# TP1_Embebidos.net
KiCad netlist of a schematic drawn in Altium Designer
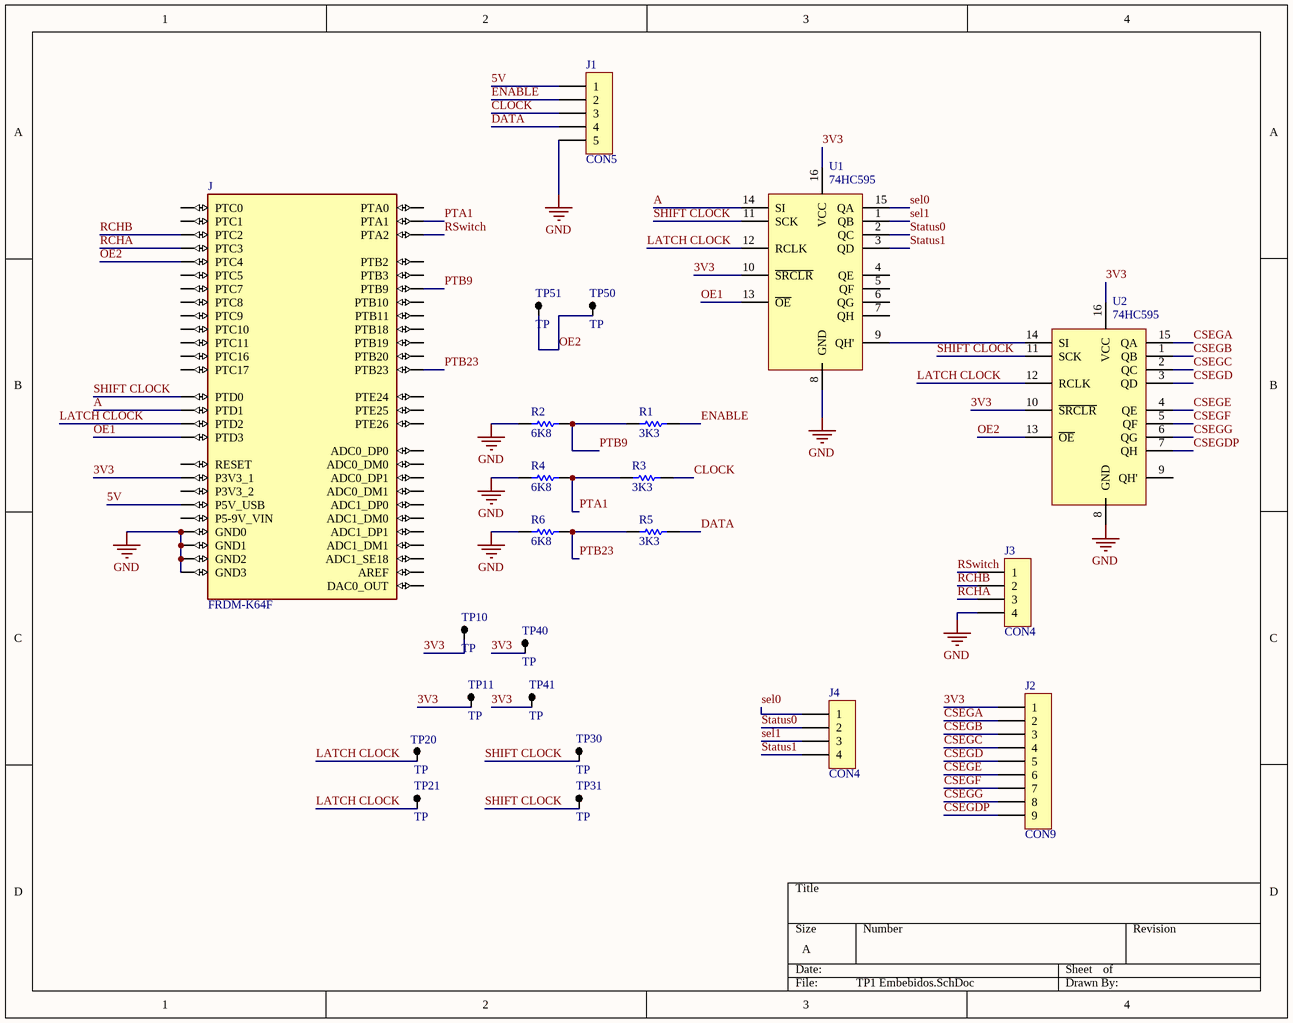
[diagram p0: TP1 Embebidos.SchDoc]

(export (version "E")
  (design (tool "Eeschema 10.0.6"))
  (components
    (comp (ref "J")
      (value "FRDM-K64F")
      (footprint "FRDM-K64F")
      (fields (field (name "MF") "NXP USA"))
      (libsource (lib "FRDM-K64F") (part "FRDM-K64F"))
    )
    (comp (ref "J1") (value "CON5") (footprint "SIP5") (libsource (lib "LIBEBAL") (part "CON5")))
    (comp (ref "J2") (value "CON9") (footprint "SIP9") (libsource (lib "LIBEBAL") (part "CON9")))
    (comp (ref "J3") (value "CON4") (footprint "SIP4") (libsource (lib "LIBEBAL") (part "CON4")))
    (comp (ref "J4") (value "CON4") (footprint "SIP4") (libsource (lib "LIBEBAL") (part "CON4")))
    (comp (ref "R1") (value "3K3") (footprint "RES400") (libsource (lib "LIBEBAL") (part "RES")))
    (comp (ref "R2") (value "6K8") (footprint "RES400") (libsource (lib "LIBEBAL") (part "RES")))
    (comp (ref "R3") (value "3K3") (footprint "RES400") (libsource (lib "LIBEBAL") (part "RES")))
    (comp (ref "R4") (value "6K8") (footprint "RES400") (libsource (lib "LIBEBAL") (part "RES")))
    (comp (ref "R5") (value "3K3") (footprint "RES400") (libsource (lib "LIBEBAL") (part "RES")))
    (comp (ref "R6") (value "6K8") (footprint "RES400") (libsource (lib "LIBEBAL") (part "RES")))
    (comp (ref "TP10") (value "TP") (footprint "TPTH") (libsource (lib "LIBEBAL") (part "TP")))
    (comp (ref "TP11") (value "TP") (footprint "TPTH") (libsource (lib "LIBEBAL") (part "TP")))
    (comp (ref "TP20") (value "TP") (footprint "TPTH") (libsource (lib "LIBEBAL") (part "TP")))
    (comp (ref "TP21") (value "TP") (footprint "TPTH") (libsource (lib "LIBEBAL") (part "TP")))
    (comp (ref "TP30") (value "TP") (footprint "TPTH") (libsource (lib "LIBEBAL") (part "TP")))
    (comp (ref "TP31") (value "TP") (footprint "TPTH") (libsource (lib "LIBEBAL") (part "TP")))
    (comp (ref "TP40") (value "TP") (footprint "TPTH") (libsource (lib "LIBEBAL") (part "TP")))
    (comp (ref "TP41") (value "TP") (footprint "TPTH") (libsource (lib "LIBEBAL") (part "TP")))
    (comp (ref "TP50") (value "TP") (footprint "TPTH") (libsource (lib "LIBEBAL") (part "TP")))
    (comp (ref "TP51") (value "TP") (footprint "TPTH") (libsource (lib "LIBEBAL") (part "TP")))
    (comp (ref "U1") (value "74HC595") (footprint "DIP16") (libsource (lib "LIBEBAL") (part "74HC595")))
    (comp (ref "U2") (value "74HC595") (footprint "DIP16") (libsource (lib "LIBEBAL") (part "74HC595")))
  )
  (nets
    (net (code "1") (name "/3V3") (class "Default")
      (node (ref "J") (pin "J3-4") (pinfunction "P3V3_1_J3-4") (pintype "bidirectional"))
      (node (ref "J2") (pin "1") (pinfunction "1_1") (pintype "passive"))
      (node (ref "TP10") (pin "1") (pinfunction "1_1") (pintype "passive"))
      (node (ref "TP11") (pin "1") (pinfunction "1_1") (pintype "passive"))
      (node (ref "TP40") (pin "1") (pinfunction "1_1") (pintype "passive"))
      (node (ref "TP41") (pin "1") (pinfunction "1_1") (pintype "passive"))
      (node (ref "U1") (pin "10") (pinfunction "~{SRCLR}_10") (pintype "passive"))
      (node (ref "U1") (pin "16") (pinfunction "VCC_16") (pintype "passive"))
      (node (ref "U2") (pin "10") (pinfunction "~{SRCLR}_10") (pintype "passive"))
      (node (ref "U2") (pin "16") (pinfunction "VCC_16") (pintype "passive"))
    )
    (net (code "2") (name "/5V") (class "Default")
      (node (ref "J") (pin "J3-10") (pinfunction "P5V_USB_J3-10") (pintype "bidirectional"))
      (node (ref "J1") (pin "1") (pinfunction "1_1") (pintype "passive"))
    )
    (net (code "3") (name "/A") (class "Default")
      (node (ref "J") (pin "J2-12") (pinfunction "PTD1_J2-12") (pintype "bidirectional"))
      (node (ref "U1") (pin "14") (pinfunction "SI_14") (pintype "passive"))
    )
    (net (code "4") (name "/CLOCK") (class "Default")
      (node (ref "J1") (pin "3") (pinfunction "3_3") (pintype "passive"))
      (node (ref "R3") (pin "2") (pinfunction "2_2") (pintype "passive"))
    )
    (net (code "5") (name "/CSEGA") (class "Default")
      (node (ref "J2") (pin "2") (pinfunction "2_2") (pintype "passive"))
      (node (ref "U2") (pin "15") (pinfunction "QA_15") (pintype "passive"))
    )
    (net (code "6") (name "/CSEGB") (class "Default")
      (node (ref "J2") (pin "3") (pinfunction "3_3") (pintype "passive"))
      (node (ref "U2") (pin "1") (pinfunction "QB_1") (pintype "passive"))
    )
    (net (code "7") (name "/CSEGC") (class "Default")
      (node (ref "J2") (pin "4") (pinfunction "4_4") (pintype "passive"))
      (node (ref "U2") (pin "2") (pinfunction "QC_2") (pintype "passive"))
    )
    (net (code "8") (name "/CSEGD") (class "Default")
      (node (ref "J2") (pin "5") (pinfunction "5_5") (pintype "passive"))
      (node (ref "U2") (pin "3") (pinfunction "QD_3") (pintype "passive"))
    )
    (net (code "9") (name "/CSEGDP") (class "Default")
      (node (ref "J2") (pin "9") (pinfunction "9_9") (pintype "passive"))
      (node (ref "U2") (pin "7") (pinfunction "QH_7") (pintype "passive"))
    )
    (net (code "10") (name "/CSEGE") (class "Default")
      (node (ref "J2") (pin "6") (pinfunction "6_6") (pintype "passive"))
      (node (ref "U2") (pin "4") (pinfunction "QE_4") (pintype "passive"))
    )
    (net (code "11") (name "/CSEGF") (class "Default")
      (node (ref "J2") (pin "7") (pinfunction "7_7") (pintype "passive"))
      (node (ref "U2") (pin "5") (pinfunction "QF_5") (pintype "passive"))
    )
    (net (code "12") (name "/CSEGG") (class "Default")
      (node (ref "J2") (pin "8") (pinfunction "8_8") (pintype "passive"))
      (node (ref "U2") (pin "6") (pinfunction "QG_6") (pintype "passive"))
    )
    (net (code "13") (name "/DATA") (class "Default")
      (node (ref "J1") (pin "4") (pinfunction "4_4") (pintype "passive"))
      (node (ref "R5") (pin "2") (pinfunction "2_2") (pintype "passive"))
    )
    (net (code "14") (name "/ENABLE") (class "Default")
      (node (ref "J1") (pin "2") (pinfunction "2_2") (pintype "passive"))
      (node (ref "R1") (pin "2") (pinfunction "2_2") (pintype "passive"))
    )
    (net (code "15") (name "/LATCH CLOCK") (class "Default")
      (node (ref "J") (pin "J2-8") (pinfunction "PTD2_J2-8") (pintype "bidirectional"))
      (node (ref "TP20") (pin "1") (pinfunction "1_1") (pintype "passive"))
      (node (ref "TP21") (pin "1") (pinfunction "1_1") (pintype "passive"))
      (node (ref "U1") (pin "12") (pinfunction "RCLK_12") (pintype "passive"))
      (node (ref "U2") (pin "12") (pinfunction "RCLK_12") (pintype "passive"))
    )
    (net (code "16") (name "/OE1") (class "Default")
      (node (ref "J") (pin "J2-10") (pinfunction "PTD3_J2-10") (pintype "bidirectional"))
      (node (ref "U1") (pin "13") (pinfunction "~{OE}_13") (pintype "passive"))
    )
    (net (code "17") (name "/OE2") (class "Default")
      (node (ref "J") (pin "J2-4") (pinfunction "PTC4_J2-4") (pintype "bidirectional"))
      (node (ref "TP50") (pin "1") (pinfunction "1_1") (pintype "passive"))
      (node (ref "TP51") (pin "1") (pinfunction "1_1") (pintype "passive"))
      (node (ref "U2") (pin "13") (pinfunction "~{OE}_13") (pintype "passive"))
    )
    (net (code "18") (name "/PTA1") (class "Default")
      (node (ref "J") (pin "J1-8") (pinfunction "PTA1_J1-8") (pintype "bidirectional"))
      (node (ref "R3") (pin "1") (pinfunction "1_1") (pintype "passive"))
      (node (ref "R4") (pin "2") (pinfunction "2_2") (pintype "passive"))
    )
    (net (code "19") (name "/PTB9") (class "Default")
      (node (ref "J") (pin "J1-6") (pinfunction "PTB9_J1-6") (pintype "bidirectional"))
      (node (ref "R1") (pin "1") (pinfunction "1_1") (pintype "passive"))
      (node (ref "R2") (pin "2") (pinfunction "2_2") (pintype "passive"))
    )
    (net (code "20") (name "/PTB23") (class "Default")
      (node (ref "J") (pin "J1-10") (pinfunction "PTB23_J1-10") (pintype "bidirectional"))
      (node (ref "R5") (pin "1") (pinfunction "1_1") (pintype "passive"))
      (node (ref "R6") (pin "2") (pinfunction "2_2") (pintype "passive"))
    )
    (net (code "21") (name "/RCHA") (class "Default")
      (node (ref "J") (pin "J1-16") (pinfunction "PTC3_J1-16") (pintype "bidirectional"))
      (node (ref "J3") (pin "3") (pinfunction "3_3") (pintype "passive"))
    )
    (net (code "22") (name "/RCHB") (class "Default")
      (node (ref "J") (pin "J1-14") (pinfunction "PTC2_J1-14") (pintype "bidirectional"))
      (node (ref "J3") (pin "2") (pinfunction "2_2") (pintype "passive"))
    )
    (net (code "23") (name "/RSwitch") (class "Default")
      (node (ref "J") (pin "J1-12") (pinfunction "PTA2_J1-12") (pintype "bidirectional"))
      (node (ref "J3") (pin "1") (pinfunction "1_1") (pintype "passive"))
    )
    (net (code "24") (name "/SHIFT CLOCK") (class "Default")
      (node (ref "J") (pin "J2-6") (pinfunction "PTD0_J2-6") (pintype "bidirectional"))
      (node (ref "TP30") (pin "1") (pinfunction "1_1") (pintype "passive"))
      (node (ref "TP31") (pin "1") (pinfunction "1_1") (pintype "passive"))
      (node (ref "U1") (pin "11") (pinfunction "SCK_11") (pintype "passive"))
      (node (ref "U2") (pin "11") (pinfunction "SCK_11") (pintype "passive"))
    )
    (net (code "25") (name "/Status0") (class "Default")
      (node (ref "J4") (pin "2") (pinfunction "2_2") (pintype "passive"))
      (node (ref "U1") (pin "2") (pinfunction "QC_2") (pintype "passive"))
    )
    (net (code "26") (name "/Status1") (class "Default")
      (node (ref "J4") (pin "4") (pinfunction "4_4") (pintype "passive"))
      (node (ref "U1") (pin "3") (pinfunction "QD_3") (pintype "passive"))
    )
    (net (code "27") (name "/sel0") (class "Default")
      (node (ref "J4") (pin "1") (pinfunction "1_1") (pintype "passive"))
      (node (ref "U1") (pin "15") (pinfunction "QA_15") (pintype "passive"))
    )
    (net (code "28") (name "/sel1") (class "Default")
      (node (ref "J4") (pin "3") (pinfunction "3_3") (pintype "passive"))
      (node (ref "U1") (pin "1") (pinfunction "QB_1") (pintype "passive"))
    )
    (net (code "29") (name "GND") (class "Default")
      (node (ref "J") (pin "J2-14") (pinfunction "GND1_J2-14") (pintype "bidirectional"))
      (node (ref "J") (pin "J2-3") (pinfunction "GND0_J2-3") (pintype "bidirectional"))
      (node (ref "J") (pin "J3-12") (pinfunction "GND2_J3-12") (pintype "bidirectional"))
      (node (ref "J") (pin "J3-14") (pinfunction "GND3_J3-14") (pintype "bidirectional"))
      (node (ref "J1") (pin "5") (pinfunction "5_5") (pintype "passive"))
      (node (ref "J3") (pin "4") (pinfunction "4_4") (pintype "passive"))
      (node (ref "R2") (pin "1") (pinfunction "1_1") (pintype "passive"))
      (node (ref "R4") (pin "1") (pinfunction "1_1") (pintype "passive"))
      (node (ref "R6") (pin "1") (pinfunction "1_1") (pintype "passive"))
      (node (ref "U1") (pin "8") (pinfunction "GND_8") (pintype "passive"))
      (node (ref "U2") (pin "8") (pinfunction "GND_8") (pintype "passive"))
    )
    (net (code "30") (name "Net-(U1-QH')") (class "Default")
      (node (ref "U1") (pin "9") (pinfunction "QH'_9") (pintype "passive"))
      (node (ref "U2") (pin "14") (pinfunction "SI_14") (pintype "passive"))
    )
    (net (code "31") (name "unconnected-(J-ADC0_DM0-PadJ2-7)") (class "Default")
      (node (ref "J") (pin "J2-7") (pinfunction "ADC0_DM0_J2-7") (pintype "bidirectional"))
    )
    (net (code "32") (name "unconnected-(J-ADC0_DM1-PadJ4-3)") (class "Default")
      (node (ref "J") (pin "J4-3") (pinfunction "ADC0_DM1_J4-3") (pintype "bidirectional"))
    )
    (net (code "33") (name "unconnected-(J-ADC0_DP0-PadJ2-5)") (class "Default")
      (node (ref "J") (pin "J2-5") (pinfunction "ADC0_DP0_J2-5") (pintype "bidirectional"))
    )
    (net (code "34") (name "unconnected-(J-ADC0_DP1-PadJ4-1)") (class "Default")
      (node (ref "J") (pin "J4-1") (pinfunction "ADC0_DP1_J4-1") (pintype "bidirectional"))
    )
    (net (code "35") (name "unconnected-(J-ADC1_DM0-PadJ2-13)") (class "Default")
      (node (ref "J") (pin "J2-13") (pinfunction "ADC1_DM0_J2-13") (pintype "bidirectional"))
    )
    (net (code "36") (name "unconnected-(J-ADC1_DM1-PadJ4-7)") (class "Default")
      (node (ref "J") (pin "J4-7") (pinfunction "ADC1_DM1_J4-7") (pintype "bidirectional"))
    )
    (net (code "37") (name "unconnected-(J-ADC1_DP0-PadJ2-11)") (class "Default")
      (node (ref "J") (pin "J2-11") (pinfunction "ADC1_DP0_J2-11") (pintype "bidirectional"))
    )
    (net (code "38") (name "unconnected-(J-ADC1_DP1-PadJ4-5)") (class "Default")
      (node (ref "J") (pin "J4-5") (pinfunction "ADC1_DP1_J4-5") (pintype "bidirectional"))
    )
    (net (code "39") (name "unconnected-(J-ADC1_SE18-PadJ2-17)") (class "Default")
      (node (ref "J") (pin "J2-17") (pinfunction "ADC1_SE18_J2-17") (pintype "bidirectional"))
    )
    (net (code "40") (name "unconnected-(J-AREF-PadJ2-16)") (class "Default")
      (node (ref "J") (pin "J2-16") (pinfunction "AREF_J2-16") (pintype "bidirectional"))
    )
    (net (code "41") (name "unconnected-(J-DAC0_OUT-PadJ4-11)") (class "Default")
      (node (ref "J") (pin "J4-11") (pinfunction "DAC0_OUT_J4-11") (pintype "bidirectional"))
    )
    (net (code "42") (name "unconnected-(J-P3V3_2-PadJ3-8)") (class "Default")
      (node (ref "J") (pin "J3-8") (pinfunction "P3V3_2_J3-8") (pintype "bidirectional"))
    )
    (net (code "43") (name "unconnected-(J-P5-9V_VIN-PadJ3-16)") (class "Default")
      (node (ref "J") (pin "J3-16") (pinfunction "P5-9V_VIN_J3-16") (pintype "bidirectional"))
    )
    (net (code "44") (name "unconnected-(J-PTA0-PadJ2-2)") (class "Default")
      (node (ref "J") (pin "J2-2") (pinfunction "PTA0_J2-2") (pintype "bidirectional"))
    )
    (net (code "45") (name "unconnected-(J-PTB2-PadJ4-2)") (class "Default")
      (node (ref "J") (pin "J4-2") (pinfunction "PTB2_J4-2") (pintype "bidirectional"))
    )
    (net (code "46") (name "unconnected-(J-PTB3-PadJ4-4)") (class "Default")
      (node (ref "J") (pin "J4-4") (pinfunction "PTB3_J4-4") (pintype "bidirectional"))
    )
    (net (code "47") (name "unconnected-(J-PTB10-PadJ4-6)") (class "Default")
      (node (ref "J") (pin "J4-6") (pinfunction "PTB10_J4-6") (pintype "bidirectional"))
    )
    (net (code "48") (name "unconnected-(J-PTB11-PadJ4-8)") (class "Default")
      (node (ref "J") (pin "J4-8") (pinfunction "PTB11_J4-8") (pintype "bidirectional"))
    )
    (net (code "49") (name "unconnected-(J-PTB18-PadJ1-1)") (class "Default")
      (node (ref "J") (pin "J1-1") (pinfunction "PTB18_J1-1") (pintype "bidirectional"))
    )
    (net (code "50") (name "unconnected-(J-PTB19-PadJ1-3)") (class "Default")
      (node (ref "J") (pin "J1-3") (pinfunction "PTB19_J1-3") (pintype "bidirectional"))
    )
    (net (code "51") (name "unconnected-(J-PTB20-PadJ4-9)") (class "Default")
      (node (ref "J") (pin "J4-9") (pinfunction "PTB20_J4-9") (pintype "bidirectional"))
    )
    (net (code "52") (name "unconnected-(J-PTC0-PadJ1-11)") (class "Default")
      (node (ref "J") (pin "J1-11") (pinfunction "PTC0_J1-11") (pintype "bidirectional"))
    )
    (net (code "53") (name "unconnected-(J-PTC1-PadJ1-5)") (class "Default")
      (node (ref "J") (pin "J1-5") (pinfunction "PTC1_J1-5") (pintype "bidirectional"))
    )
    (net (code "54") (name "unconnected-(J-PTC5-PadJ1-15)") (class "Default")
      (node (ref "J") (pin "J1-15") (pinfunction "PTC5_J1-15") (pintype "bidirectional"))
    )
    (net (code "55") (name "unconnected-(J-PTC7-PadJ1-13)") (class "Default")
      (node (ref "J") (pin "J1-13") (pinfunction "PTC7_J1-13") (pintype "bidirectional"))
    )
    (net (code "56") (name "unconnected-(J-PTC8-PadJ1-7)") (class "Default")
      (node (ref "J") (pin "J1-7") (pinfunction "PTC8_J1-7") (pintype "bidirectional"))
    )
    (net (code "57") (name "unconnected-(J-PTC9-PadJ1-9)") (class "Default")
      (node (ref "J") (pin "J1-9") (pinfunction "PTC9_J1-9") (pintype "bidirectional"))
    )
    (net (code "58") (name "unconnected-(J-PTC10-PadJ4-12)") (class "Default")
      (node (ref "J") (pin "J4-12") (pinfunction "PTC10_J4-12") (pintype "bidirectional"))
    )
    (net (code "59") (name "unconnected-(J-PTC11-PadJ4-10)") (class "Default")
      (node (ref "J") (pin "J4-10") (pinfunction "PTC11_J4-10") (pintype "bidirectional"))
    )
    (net (code "60") (name "unconnected-(J-PTC16-PadJ1-2)") (class "Default")
      (node (ref "J") (pin "J1-2") (pinfunction "PTC16_J1-2") (pintype "bidirectional"))
    )
    (net (code "61") (name "unconnected-(J-PTC17-PadJ1-4)") (class "Default")
      (node (ref "J") (pin "J1-4") (pinfunction "PTC17_J1-4") (pintype "bidirectional"))
    )
    (net (code "62") (name "unconnected-(J-PTE24-PadJ2-20)") (class "Default")
      (node (ref "J") (pin "J2-20") (pinfunction "PTE24_J2-20") (pintype "bidirectional"))
    )
    (net (code "63") (name "unconnected-(J-PTE25-PadJ2-18)") (class "Default")
      (node (ref "J") (pin "J2-18") (pinfunction "PTE25_J2-18") (pintype "bidirectional"))
    )
    (net (code "64") (name "unconnected-(J-PTE26-PadJ2-1)") (class "Default")
      (node (ref "J") (pin "J2-1") (pinfunction "PTE26_J2-1") (pintype "bidirectional"))
    )
    (net (code "65") (name "unconnected-(J-RESET-PadJ3-6)") (class "Default")
      (node (ref "J") (pin "J3-6") (pinfunction "RESET_J3-6") (pintype "bidirectional"))
    )
    (net (code "66") (name "unconnected-(U1-QE-Pad4)") (class "Default")
      (node (ref "U1") (pin "4") (pinfunction "QE_4") (pintype "passive"))
    )
    (net (code "67") (name "unconnected-(U1-QF-Pad5)") (class "Default")
      (node (ref "U1") (pin "5") (pinfunction "QF_5") (pintype "passive"))
    )
    (net (code "68") (name "unconnected-(U1-QG-Pad6)") (class "Default")
      (node (ref "U1") (pin "6") (pinfunction "QG_6") (pintype "passive"))
    )
    (net (code "69") (name "unconnected-(U1-QH-Pad7)") (class "Default")
      (node (ref "U1") (pin "7") (pinfunction "QH_7") (pintype "passive"))
    )
    (net (code "70") (name "unconnected-(U2-QH'-Pad9)") (class "Default")
      (node (ref "U2") (pin "9") (pinfunction "QH'_9") (pintype "passive"))
    )
  )
)
